# SenseBox-Eye_v1_4.net
KiCad netlist of a schematic drawn in EAGLE
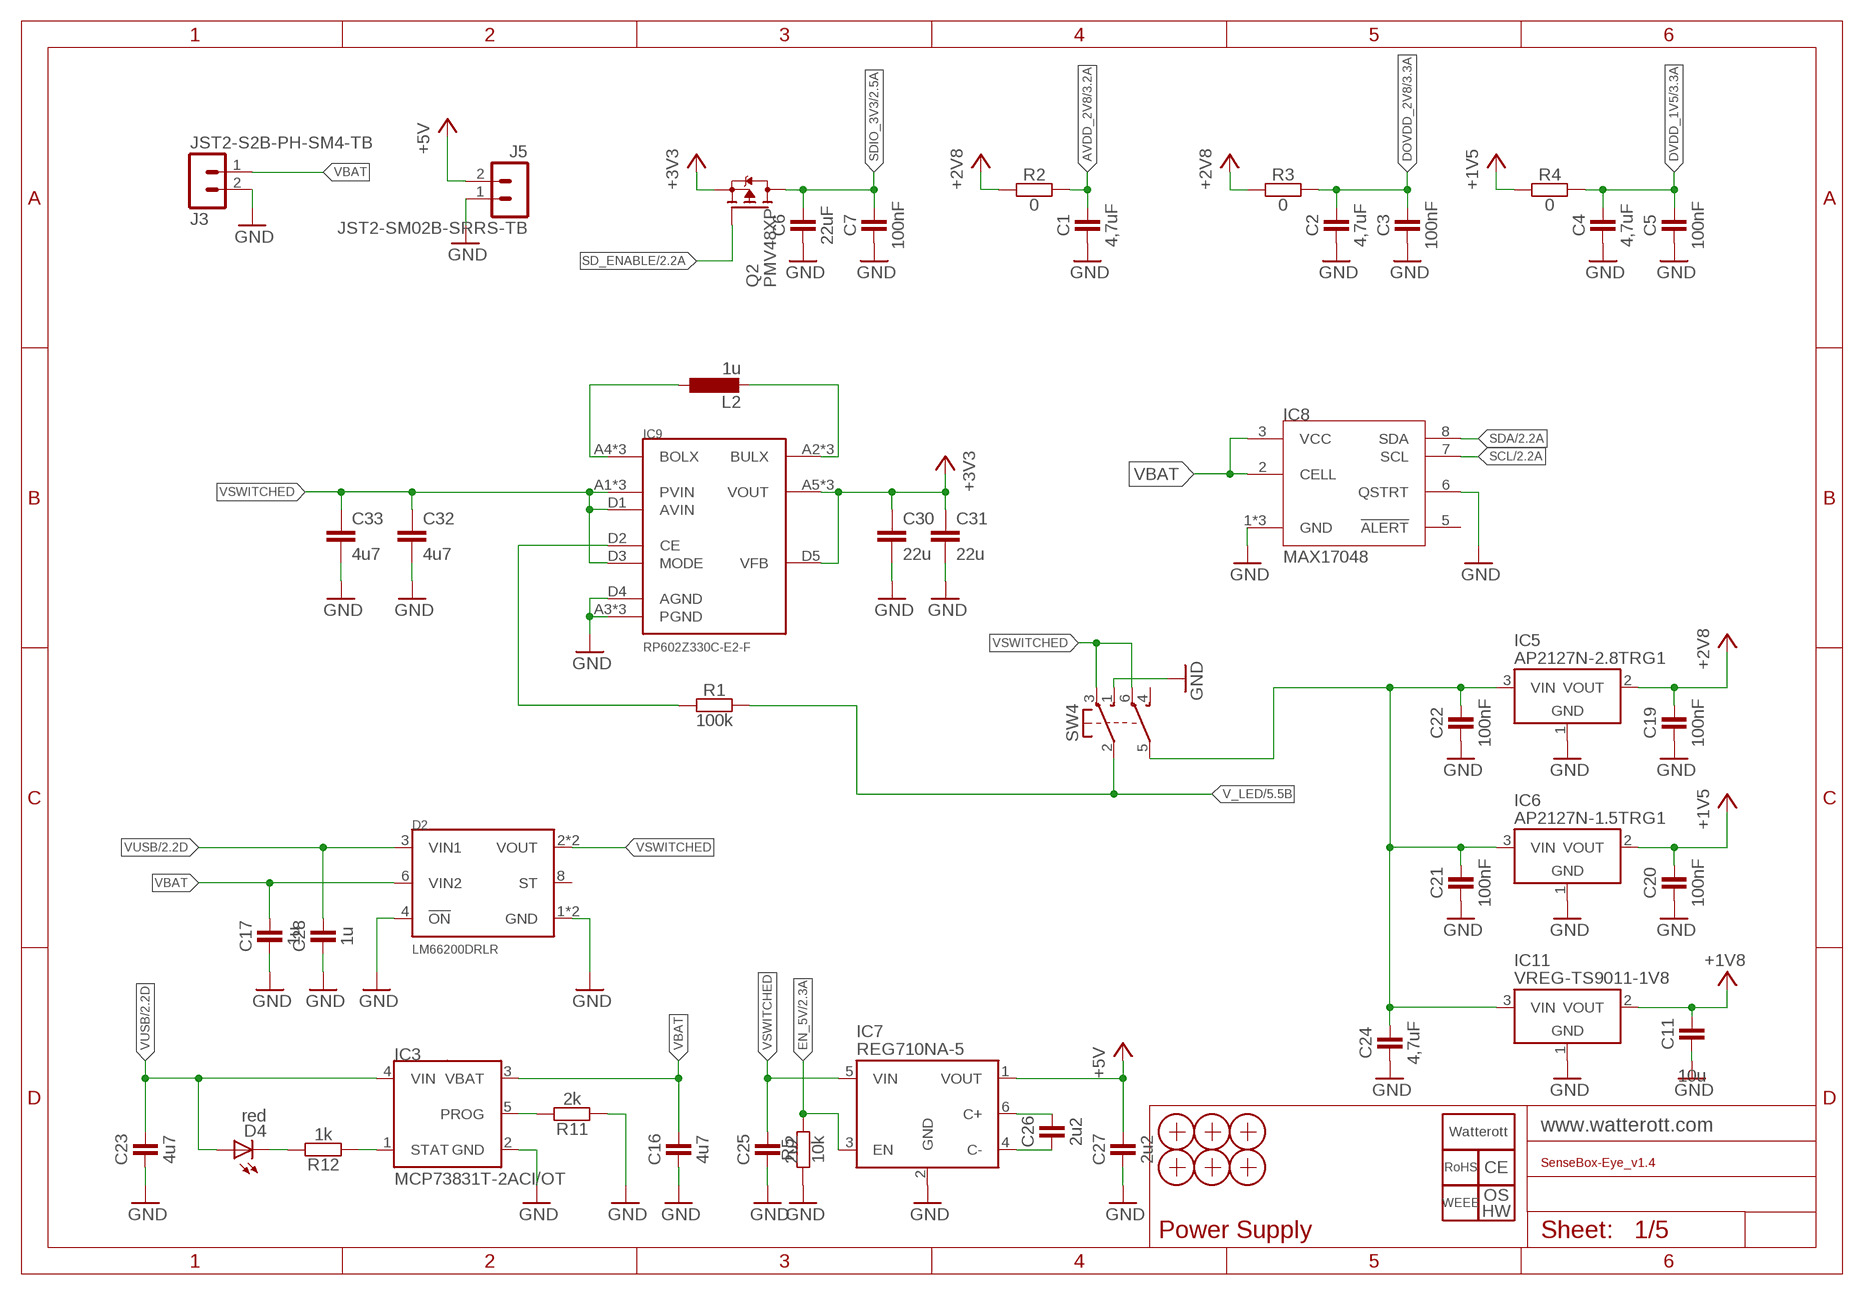
[diagram p0: schematic, sheet 1]
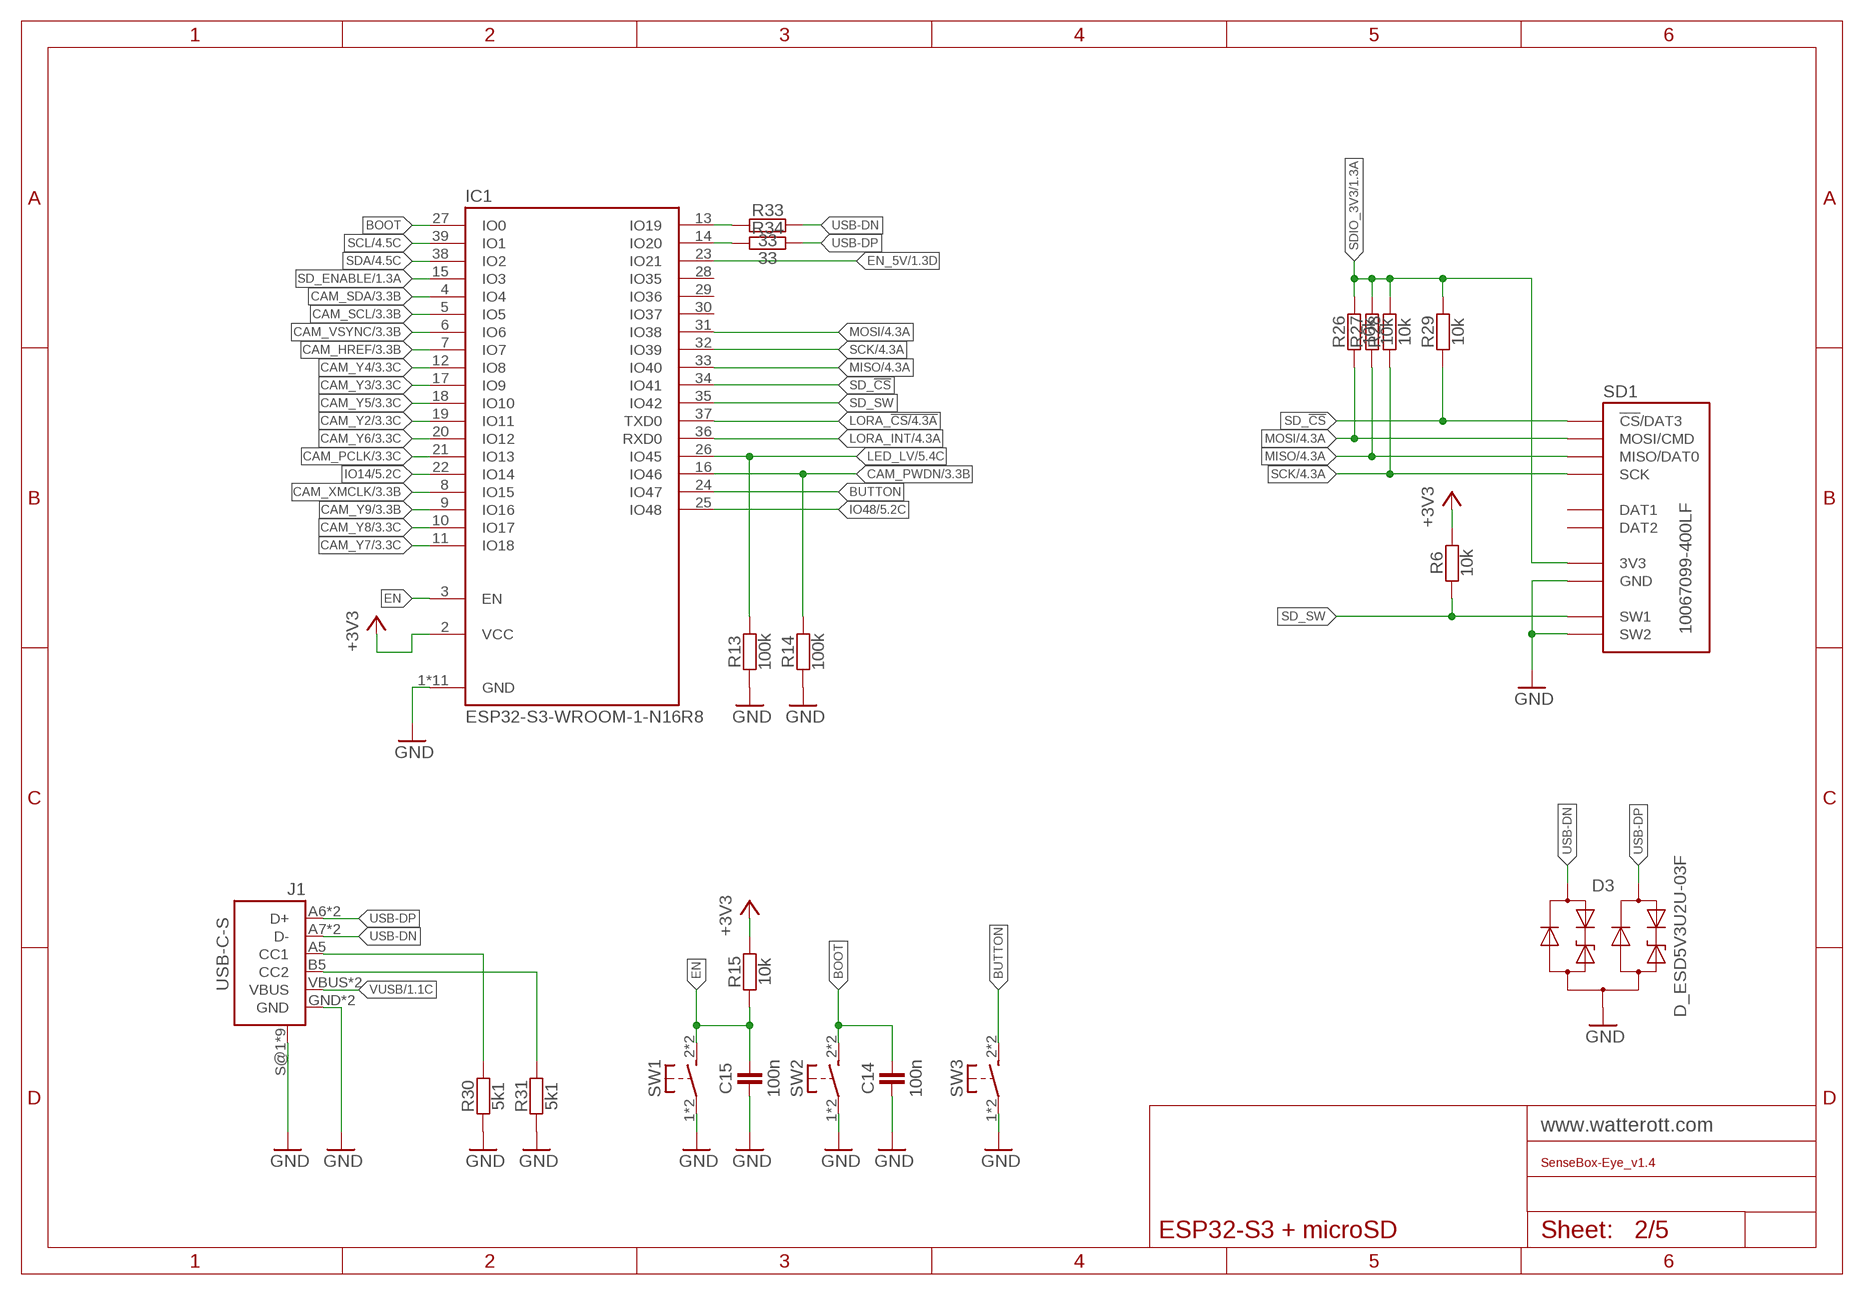
[diagram p1: schematic, sheet 2]
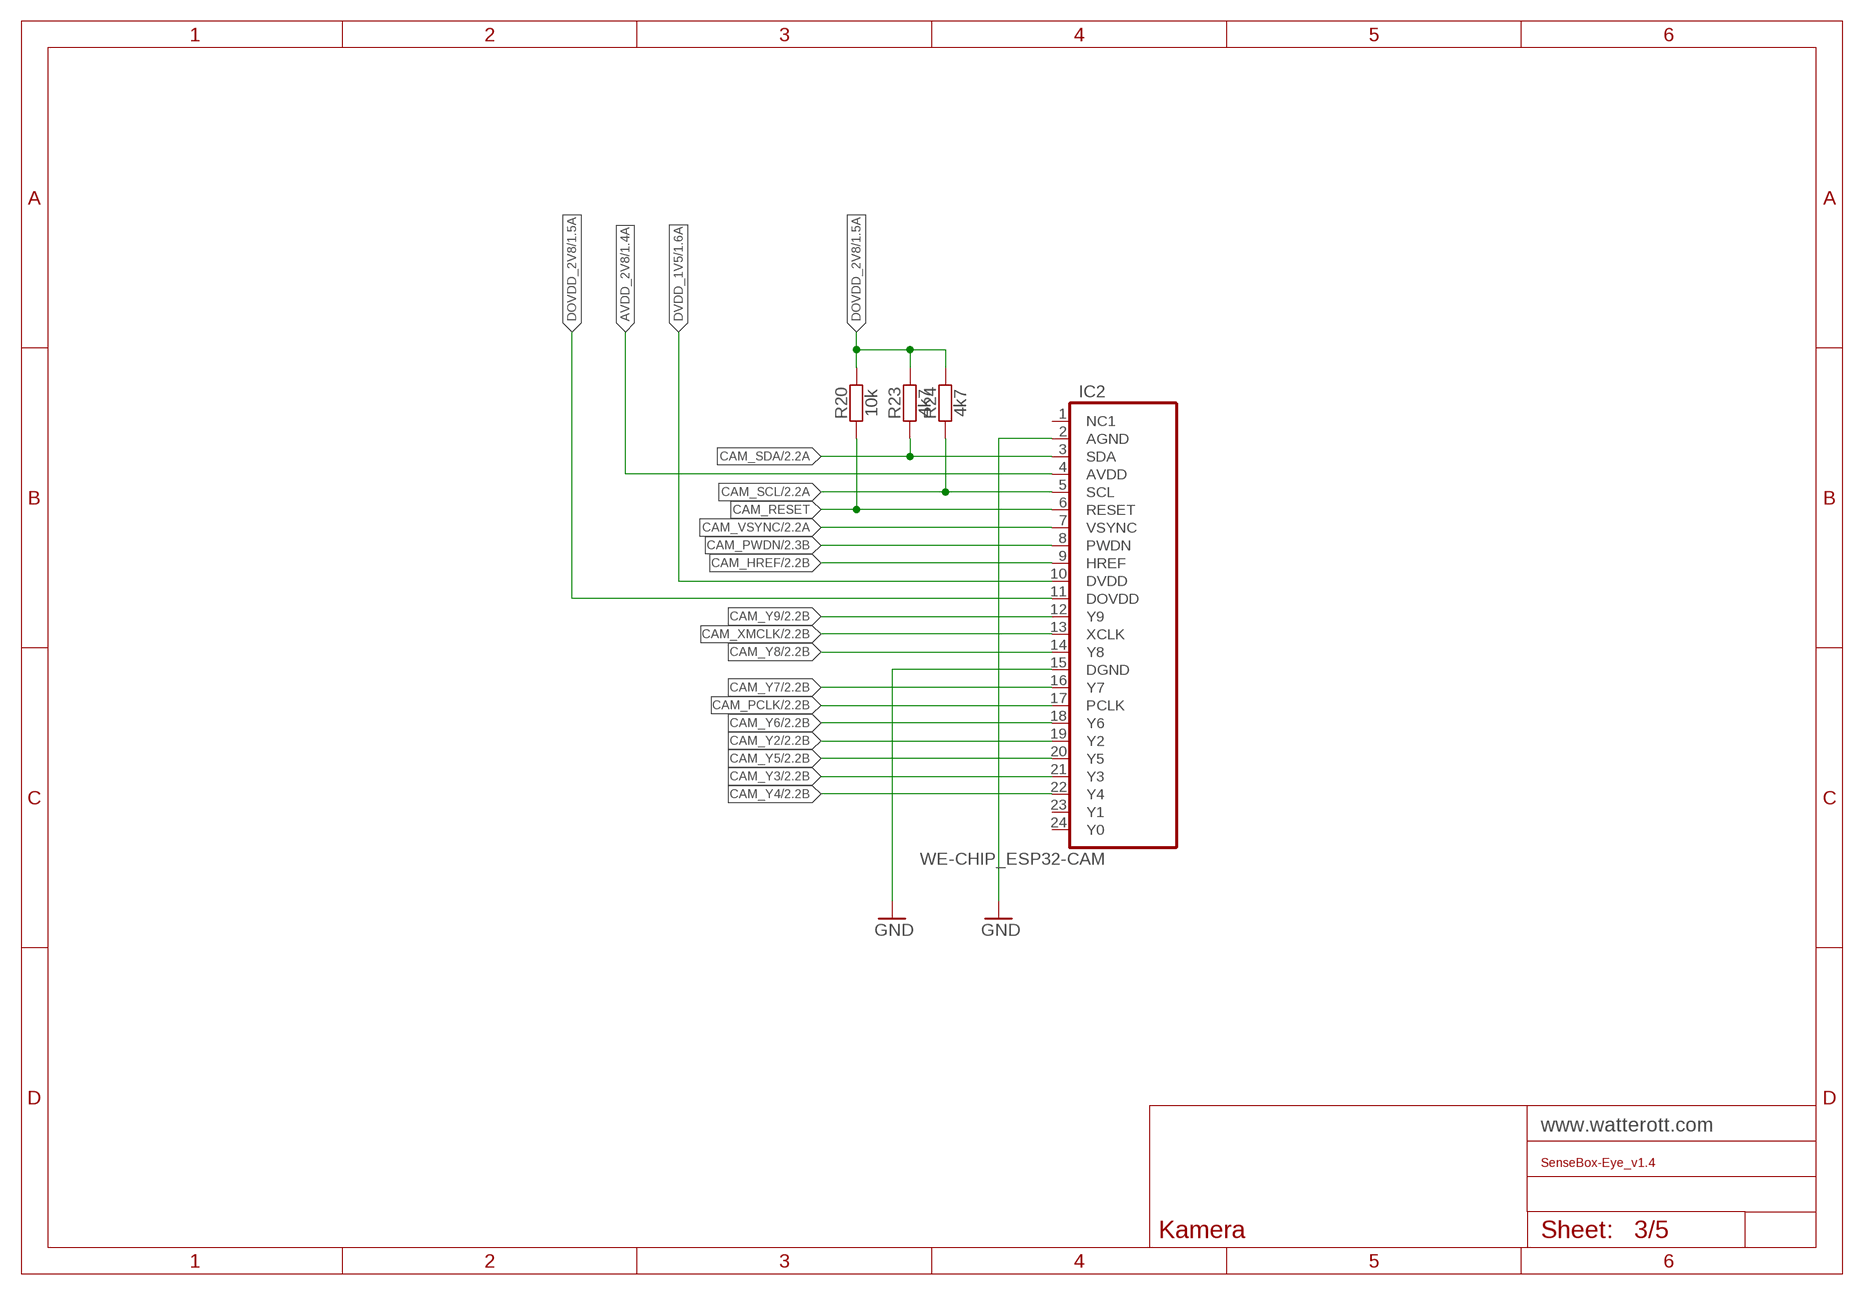
[diagram p2: schematic, sheet 3]
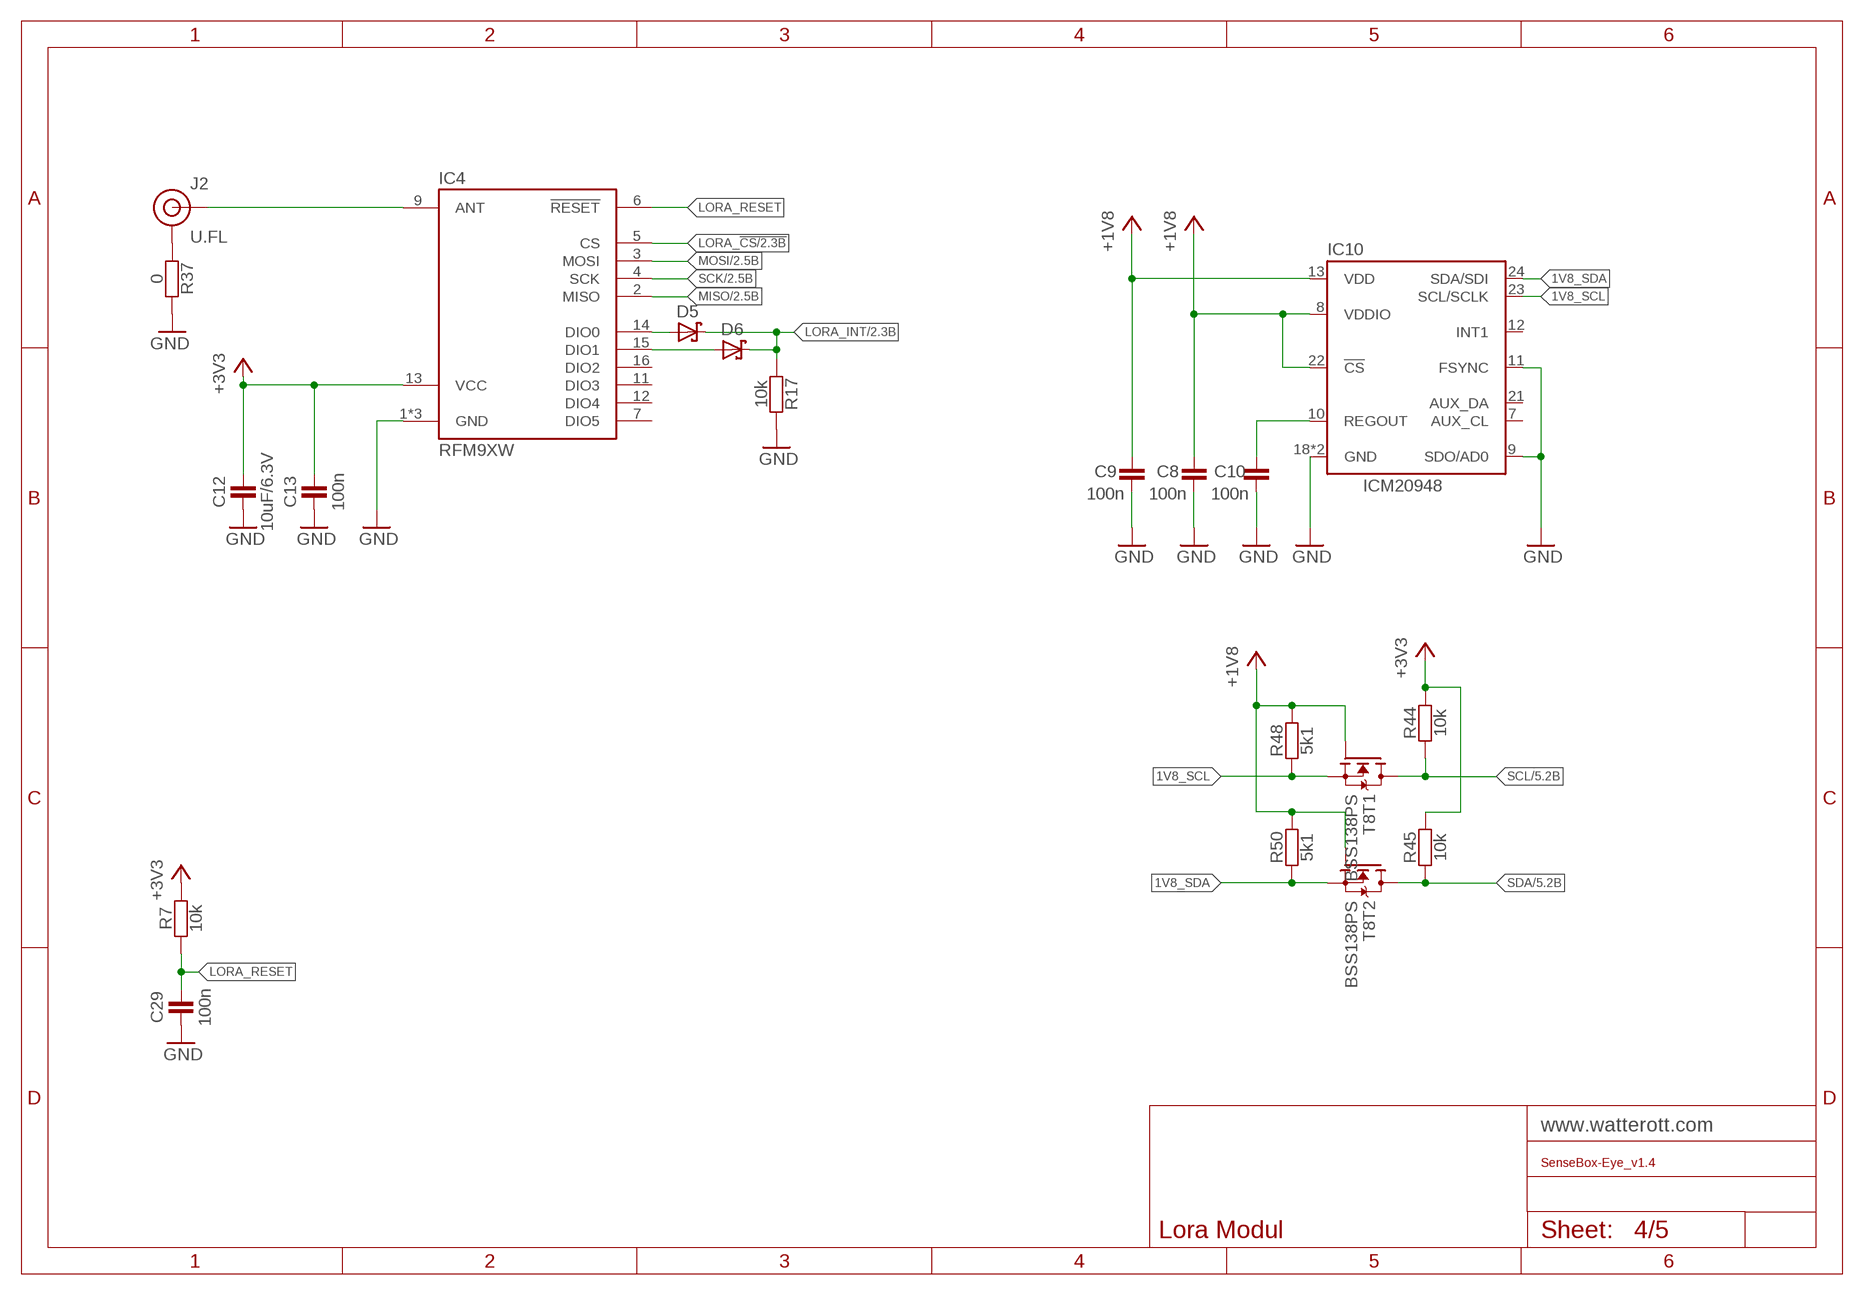
[diagram p3: schematic, sheet 4]
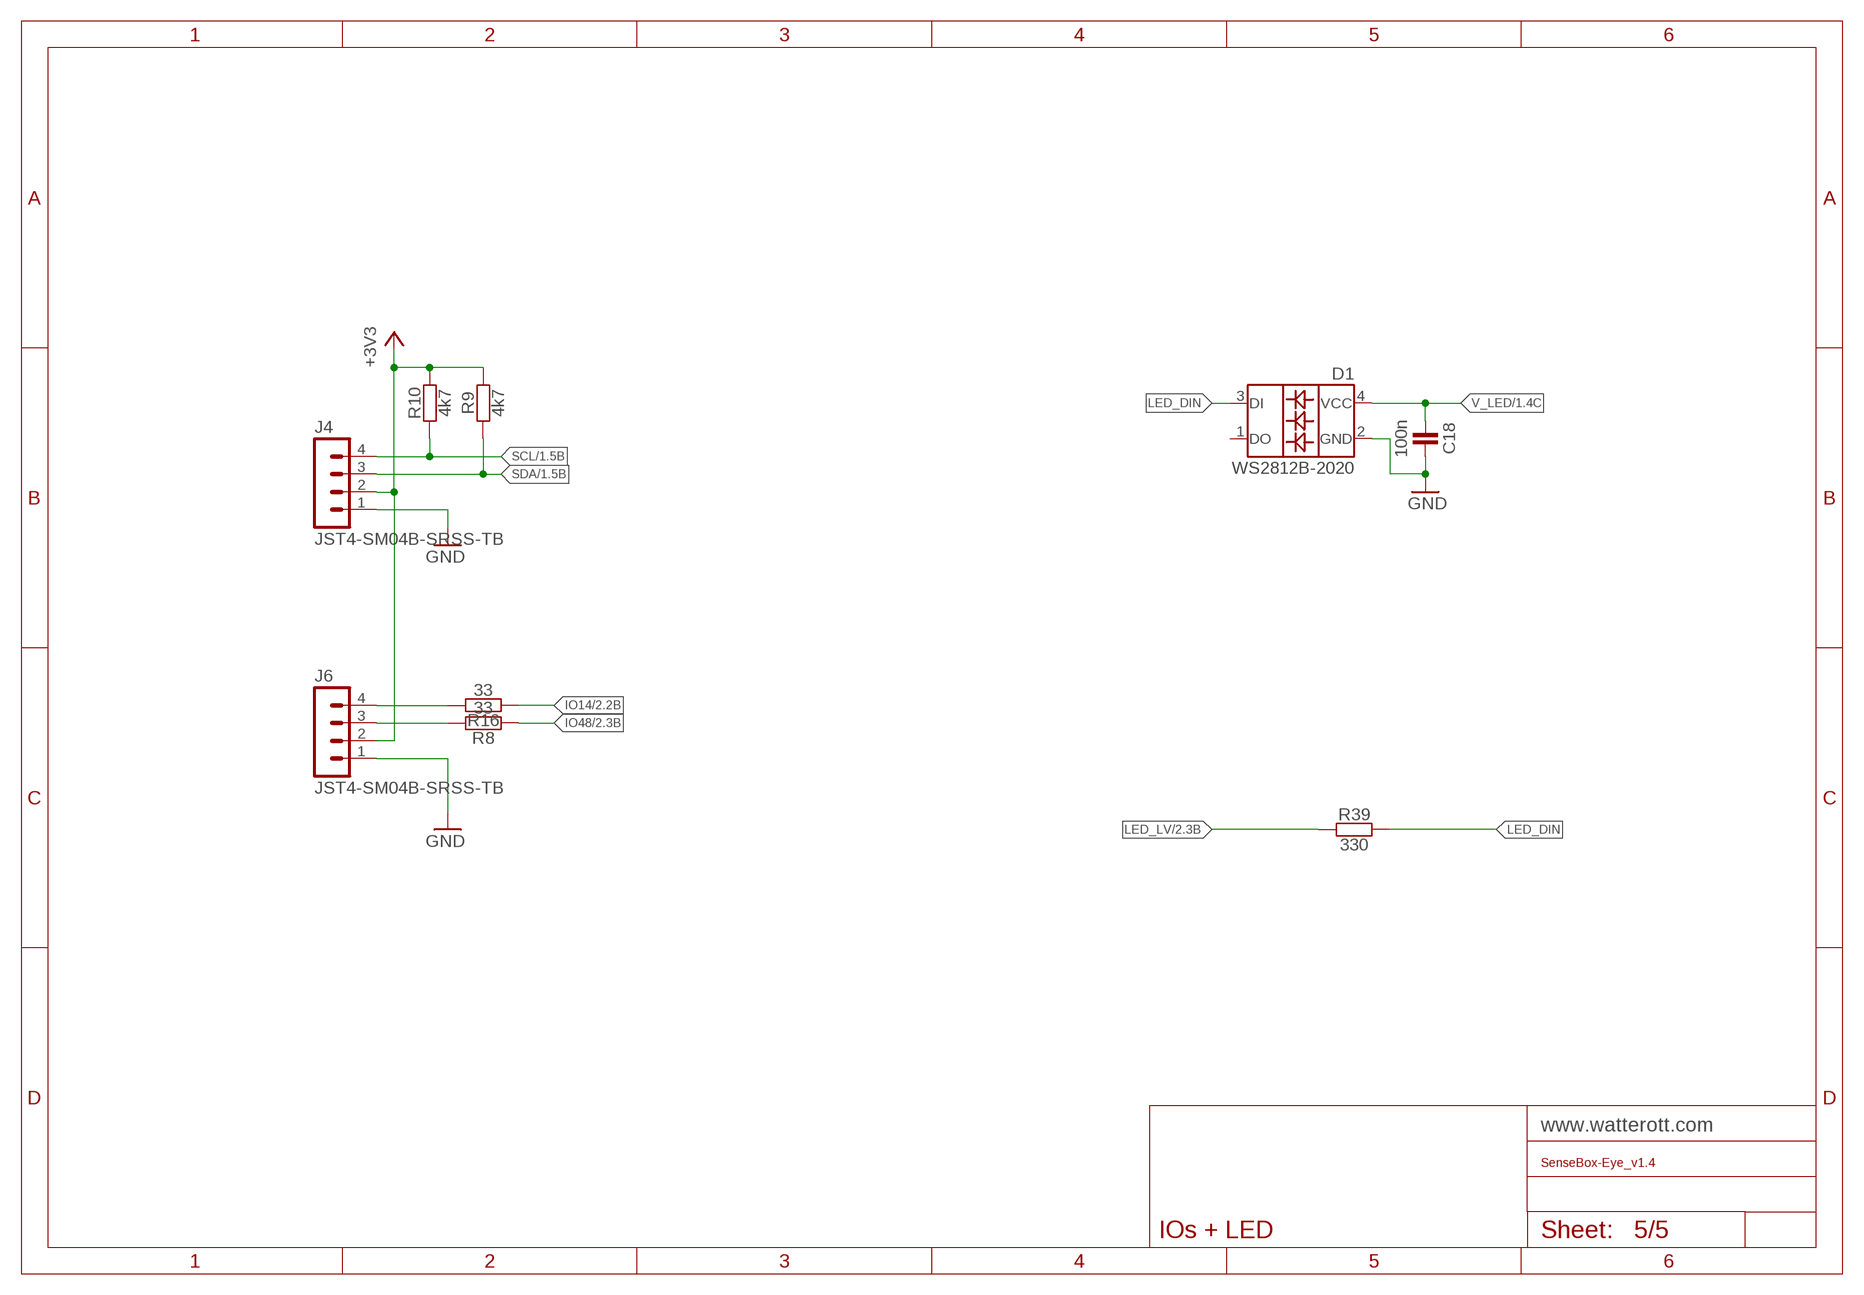
[diagram p4: schematic, sheet 5]

(export (version "E")
  (design (tool "Eeschema 10.0.6"))
  (components
    (comp (ref "IC2")
      (value "WE-CHIP_ESP32-CAM")
      (footprint "eagle-import:WE-CHIP_FPC24-0.5-CAM")
      (libsource (lib "eagle-import") (part "WE-CHIP_ESP32-CAM"))
    )
    (comp (ref "R20")
      (value "10k")
      (footprint "eagle-import:C0402")
      (libsource (lib "eagle-import") (part "RESISTOR-0402"))
    )
    (comp (ref "R23")
      (value "4k7")
      (footprint "eagle-import:C0402")
      (libsource (lib "eagle-import") (part "RESISTOR-0402"))
    )
    (comp (ref "R24")
      (value "4k7")
      (footprint "eagle-import:C0402")
      (libsource (lib "eagle-import") (part "RESISTOR-0402"))
    )
    (comp (ref "C14")
      (value "100n")
      (footprint "eagle-import:C0402")
      (libsource (lib "eagle-import") (part "CAPACITOR-0402"))
    )
    (comp (ref "C15")
      (value "100n")
      (footprint "eagle-import:C0402")
      (libsource (lib "eagle-import") (part "CAPACITOR-0402"))
    )
    (comp (ref "D3")
      (value "D_ESD5V3U2U-03F")
      (footprint "eagle-import:SOT723")
      (libsource (lib "eagle-import") (part "D_ESD5V3U2U-03F"))
    )
    (comp (ref "IC1")
      (value "ESP32-S3-WROOM-1-N16R8")
      (footprint "eagle-import:ESP32-S3-WROOM-1")
      (libsource (lib "eagle-import") (part "ESP32_S3-WROOM-1"))
    )
    (comp (ref "J1")
      (value "USB-C-S")
      (footprint "eagle-import:USB-C-S")
      (libsource (lib "eagle-import") (part "USB-C-S"))
    )
    (comp (ref "R6")
      (value "10k")
      (footprint "eagle-import:C0402")
      (libsource (lib "eagle-import") (part "RESISTOR-0402"))
    )
    (comp (ref "R13")
      (value "100k")
      (footprint "eagle-import:C0402")
      (libsource (lib "eagle-import") (part "RESISTOR-0402"))
    )
    (comp (ref "R14")
      (value "100k")
      (footprint "eagle-import:C0402")
      (libsource (lib "eagle-import") (part "RESISTOR-0402"))
    )
    (comp (ref "R15")
      (value "10k")
      (footprint "eagle-import:C0402")
      (libsource (lib "eagle-import") (part "RESISTOR-0402"))
    )
    (comp (ref "R26")
      (value "10k")
      (footprint "eagle-import:C0402")
      (libsource (lib "eagle-import") (part "RESISTOR-0402"))
    )
    (comp (ref "R27")
      (value "10k")
      (footprint "eagle-import:C0402")
      (libsource (lib "eagle-import") (part "RESISTOR-0402"))
    )
    (comp (ref "R28")
      (value "10k")
      (footprint "eagle-import:C0402")
      (libsource (lib "eagle-import") (part "RESISTOR-0402"))
    )
    (comp (ref "R29")
      (value "10k")
      (footprint "eagle-import:C0402")
      (libsource (lib "eagle-import") (part "RESISTOR-0402"))
    )
    (comp (ref "R30")
      (value "5k1")
      (footprint "eagle-import:C0402")
      (libsource (lib "eagle-import") (part "RESISTOR-0402"))
    )
    (comp (ref "R31")
      (value "5k1")
      (footprint "eagle-import:C0402")
      (libsource (lib "eagle-import") (part "RESISTOR-0402"))
    )
    (comp (ref "R33")
      (value "33")
      (footprint "eagle-import:C0402")
      (libsource (lib "eagle-import") (part "RESISTOR-0402"))
    )
    (comp (ref "R34")
      (value "33")
      (footprint "eagle-import:C0402")
      (libsource (lib "eagle-import") (part "RESISTOR-0402"))
    )
    (comp (ref "SD1")
      (value "10067099-400LF")
      (footprint "eagle-import:SD_47309XXXX")
      (libsource (lib "eagle-import") (part "SD-CARD-MSD47"))
    )
    (comp (ref "SW1")
      (value "SW-TACTILE-TL3305")
      (footprint "eagle-import:TL3305")
      (libsource (lib "eagle-import") (part "SW-TACTILE-TL3305"))
    )
    (comp (ref "SW2")
      (value "SW-TACTILE-TL3305")
      (footprint "eagle-import:TL3305")
      (libsource (lib "eagle-import") (part "SW-TACTILE-TL3305"))
    )
    (comp (ref "SW3")
      (value "SW-TACTILE-TL3305")
      (footprint "eagle-import:TL3305")
      (libsource (lib "eagle-import") (part "SW-TACTILE-TL3305"))
    )
    (comp (ref "C18")
      (value "100n")
      (footprint "eagle-import:C0402")
      (libsource (lib "eagle-import") (part "CAPACITOR-0402"))
    )
    (comp (ref "D1")
      (value "WS2812B-2020")
      (footprint "eagle-import:WS2812_2020")
      (libsource (lib "eagle-import") (part "WS2812B-2020"))
    )
    (comp (ref "J4")
      (value "JST4-SM04B-SRSS-TB")
      (footprint "eagle-import:JST_SM04B-SRSS-TB")
      (libsource (lib "eagle-import") (part "JST4-SM04B-SRSS-TB"))
    )
    (comp (ref "J6")
      (value "JST4-SM04B-SRSS-TB")
      (footprint "eagle-import:JST_SM04B-SRSS-TB")
      (libsource (lib "eagle-import") (part "JST4-SM04B-SRSS-TB"))
    )
    (comp (ref "R8")
      (value "33")
      (footprint "eagle-import:C0402")
      (libsource (lib "eagle-import") (part "RESISTOR-0402"))
    )
    (comp (ref "R9")
      (value "4k7")
      (footprint "eagle-import:C0402")
      (libsource (lib "eagle-import") (part "RESISTOR-0402"))
    )
    (comp (ref "R10")
      (value "4k7")
      (footprint "eagle-import:C0402")
      (libsource (lib "eagle-import") (part "RESISTOR-0402"))
    )
    (comp (ref "R16")
      (value "33")
      (footprint "eagle-import:C0402")
      (libsource (lib "eagle-import") (part "RESISTOR-0402"))
    )
    (comp (ref "R39")
      (value "330")
      (footprint "eagle-import:C0402")
      (libsource (lib "eagle-import") (part "RESISTOR-0402"))
    )
    (comp (ref "C1")
      (value "4,7uF")
      (footprint "eagle-import:C0402")
      (libsource (lib "eagle-import") (part "CAPACITOR-0402"))
    )
    (comp (ref "C2")
      (value "4,7uF")
      (footprint "eagle-import:C0402")
      (libsource (lib "eagle-import") (part "CAPACITOR-0402"))
    )
    (comp (ref "C3")
      (value "100nF")
      (footprint "eagle-import:C0402")
      (libsource (lib "eagle-import") (part "CAPACITOR-0402"))
    )
    (comp (ref "C4")
      (value "4,7uF")
      (footprint "eagle-import:C0402")
      (libsource (lib "eagle-import") (part "CAPACITOR-0402"))
    )
    (comp (ref "C5")
      (value "100nF")
      (footprint "eagle-import:C0402")
      (libsource (lib "eagle-import") (part "CAPACITOR-0402"))
    )
    (comp (ref "C6")
      (value "22uF")
      (footprint "eagle-import:C0402")
      (libsource (lib "eagle-import") (part "CAPACITOR-0402"))
    )
    (comp (ref "C7")
      (value "100nF")
      (footprint "eagle-import:C0402")
      (libsource (lib "eagle-import") (part "CAPACITOR-0402"))
    )
    (comp (ref "C11")
      (value "10u")
      (footprint "eagle-import:C0402")
      (libsource (lib "eagle-import") (part "CAPACITOR-0402"))
    )
    (comp (ref "C16")
      (value "4u7")
      (footprint "eagle-import:C0402")
      (libsource (lib "eagle-import") (part "CAPACITOR-0402"))
    )
    (comp (ref "C17")
      (value "1u")
      (footprint "eagle-import:C0402")
      (libsource (lib "eagle-import") (part "CAPACITOR-0402"))
    )
    (comp (ref "C19")
      (value "100nF")
      (footprint "eagle-import:C0402")
      (libsource (lib "eagle-import") (part "CAPACITOR-0402"))
    )
    (comp (ref "C20")
      (value "100nF")
      (footprint "eagle-import:C0402")
      (libsource (lib "eagle-import") (part "CAPACITOR-0402"))
    )
    (comp (ref "C21")
      (value "100nF")
      (footprint "eagle-import:C0402")
      (libsource (lib "eagle-import") (part "CAPACITOR-0402"))
    )
    (comp (ref "C22")
      (value "100nF")
      (footprint "eagle-import:C0402")
      (libsource (lib "eagle-import") (part "CAPACITOR-0402"))
    )
    (comp (ref "C23")
      (value "4u7")
      (footprint "eagle-import:C0402")
      (libsource (lib "eagle-import") (part "CAPACITOR-0402"))
    )
    (comp (ref "C24")
      (value "4,7uF")
      (footprint "eagle-import:C0402")
      (libsource (lib "eagle-import") (part "CAPACITOR-0402"))
    )
    (comp (ref "C25")
      (value "2u2")
      (footprint "eagle-import:C0402")
      (libsource (lib "eagle-import") (part "CAPACITOR-0402"))
    )
    (comp (ref "C26")
      (value "2u2")
      (footprint "eagle-import:C0402")
      (libsource (lib "eagle-import") (part "CAPACITOR-0402"))
    )
    (comp (ref "C27")
      (value "2u2")
      (footprint "eagle-import:C0402")
      (libsource (lib "eagle-import") (part "CAPACITOR-0402"))
    )
    (comp (ref "C28")
      (value "1u")
      (footprint "eagle-import:C0402")
      (libsource (lib "eagle-import") (part "CAPACITOR-0402"))
    )
    (comp (ref "C30")
      (value "22u")
      (footprint "eagle-import:0805N")
      (fields (field (name "VOLTAGE") "6V3"))
      (libsource (lib "eagle-import") (part "C_0805N_22U"))
    )
    (comp (ref "C31")
      (value "22u")
      (footprint "eagle-import:0805N")
      (fields (field (name "VOLTAGE") "6V3"))
      (libsource (lib "eagle-import") (part "C_0805N_22U"))
    )
    (comp (ref "C32")
      (value "4u7")
      (footprint "eagle-import:0603N")
      (fields (field (name "VOLTAGE") "6V3"))
      (libsource (lib "eagle-import") (part "C_0603N_4U7"))
    )
    (comp (ref "C33")
      (value "4u7")
      (footprint "eagle-import:0603N")
      (fields (field (name "VOLTAGE") "6V3"))
      (libsource (lib "eagle-import") (part "C_0603N_4U7"))
    )
    (comp (ref "D2")
      (value "LM66200DRLR")
      (footprint "eagle-import:SOT-5X3")
      (libsource (lib "eagle-import") (part "LM66200"))
    )
    (comp (ref "D4")
      (value "red")
      (footprint "eagle-import:0603N")
      (libsource (lib "eagle-import") (part "LED_0603N_RED"))
    )
    (comp (ref "IC3")
      (value "MCP73831T-2ACI/OT")
      (footprint "eagle-import:SOT23-5")
      (libsource (lib "eagle-import") (part "MCP73831_SOT23-5_MCP73831T-2ACI/OT"))
    )
    (comp (ref "IC5")
      (value "AP2127N-2.8TRG1")
      (footprint "eagle-import:SOT23")
      (libsource (lib "eagle-import") (part "VREG-TS9011-3V3"))
    )
    (comp (ref "IC6")
      (value "AP2127N-1.5TRG1")
      (footprint "eagle-import:SOT23")
      (libsource (lib "eagle-import") (part "VREG-TS9011-3V3"))
    )
    (comp (ref "IC7")
      (value "REG710NA-5")
      (footprint "eagle-import:SOT23-6")
      (libsource (lib "eagle-import") (part "REG710NA-5"))
    )
    (comp (ref "IC8")
      (value "MAX17048")
      (footprint "eagle-import:UDFN8_2020")
      (libsource (lib "eagle-import") (part "MAX1704X"))
    )
    (comp (ref "IC9")
      (value "RP602Z330C-E2-F")
      (footprint "eagle-import:WLCSP-20-P1")
      (libsource (lib "eagle-import") (part "RP602_WLCSP-20-P1_RP602Z330C-E2-F"))
    )
    (comp (ref "IC11")
      (value "VREG-TS9011-1V8")
      (footprint "eagle-import:SOT23")
      (libsource (lib "eagle-import") (part "VREG-TS9011-1V8"))
    )
    (comp (ref "J3")
      (value "JST2-S2B-PH-SM4-TB")
      (footprint "eagle-import:JST_S2B-PH-SM4-TB")
      (libsource (lib "eagle-import") (part "JST2-S2B-PH-SM4-TB"))
    )
    (comp (ref "J5")
      (value "JST2-SM02B-SRRS-TB")
      (footprint "eagle-import:JST_SM02B-SRSS-TB")
      (libsource (lib "eagle-import") (part "JST2-SM02B-SRRS-TB"))
    )
    (comp (ref "L2")
      (value "1u")
      (footprint "eagle-import:5040")
      (libsource (lib "eagle-import") (part "L_5040_WE-LQS-1U"))
    )
    (comp (ref "LOGO2")
      (value "LOGO_CE-5")
      (footprint "eagle-import:CE_5MM")
      (libsource (lib "eagle-import") (part "LOGO_CE-5"))
    )
    (comp (ref "LOGO3")
      (value "LOGO_OSHW-2")
      (footprint "eagle-import:OSHW_2MM")
      (libsource (lib "eagle-import") (part "LOGO_OSHW-2"))
    )
    (comp (ref "LOGO4")
      (value "LOGO_ROHS-2")
      (footprint "eagle-import:ROHS_2MM")
      (libsource (lib "eagle-import") (part "LOGO_ROHS-2"))
    )
    (comp (ref "LOGO5")
      (value "LOGO_WEEE-4")
      (footprint "eagle-import:WEEE_4MM")
      (libsource (lib "eagle-import") (part "LOGO_WEEE-4"))
    )
    (comp (ref "LOGO6")
      (value "LOGO_SPARK-2")
      (footprint "eagle-import:SPARK_2MM")
      (libsource (lib "eagle-import") (part "LOGO_SPARK-2"))
    )
    (comp (ref "Q2")
      (value "PMV48XP")
      (footprint "eagle-import:SOT23")
      (fields (field (name "VOLTAGE") "20"))
      (libsource (lib "eagle-import") (part "MOSFET-P_SOT23'_PMV48XP"))
    )
    (comp (ref "R1")
      (value "100k")
      (footprint "eagle-import:C0402")
      (libsource (lib "eagle-import") (part "RESISTOR-0402"))
    )
    (comp (ref "R2")
      (value "0")
      (footprint "eagle-import:C0402")
      (libsource (lib "eagle-import") (part "RESISTOR-0402"))
    )
    (comp (ref "R3")
      (value "0")
      (footprint "eagle-import:C0402")
      (libsource (lib "eagle-import") (part "RESISTOR-0402"))
    )
    (comp (ref "R4")
      (value "0")
      (footprint "eagle-import:C0402")
      (libsource (lib "eagle-import") (part "RESISTOR-0402"))
    )
    (comp (ref "R5")
      (value "10k")
      (footprint "eagle-import:C0402")
      (libsource (lib "eagle-import") (part "RESISTOR-0402"))
    )
    (comp (ref "R11")
      (value "2k")
      (footprint "eagle-import:C0402")
      (libsource (lib "eagle-import") (part "RESISTOR-0402"))
    )
    (comp (ref "R12")
      (value "1k")
      (footprint "eagle-import:C0402")
      (libsource (lib "eagle-import") (part "RESISTOR-0402"))
    )
    (comp (ref "SW4")
      (value "SW-2UM-CUS22B")
      (footprint "eagle-import:CUS22B")
      (libsource (lib "eagle-import") (part "SW-2UM-CUS22B"))
    )
    (comp (ref "X1")
      (value "PASSER-04")
      (footprint "eagle-import:PASSER_04MM")
      (libsource (lib "eagle-import") (part "PASSER-04"))
    )
    (comp (ref "X2")
      (value "PASSER-04")
      (footprint "eagle-import:PASSER_04MM")
      (libsource (lib "eagle-import") (part "PASSER-04"))
    )
    (comp (ref "X3")
      (value "PASSER-04")
      (footprint "eagle-import:PASSER_04MM")
      (libsource (lib "eagle-import") (part "PASSER-04"))
    )
    (comp (ref "X4")
      (value "PASSER-04")
      (footprint "eagle-import:PASSER_04MM")
      (libsource (lib "eagle-import") (part "PASSER-04"))
    )
    (comp (ref "X5")
      (value "PASSER-04")
      (footprint "eagle-import:PASSER_04MM")
      (libsource (lib "eagle-import") (part "PASSER-04"))
    )
    (comp (ref "X6")
      (value "PASSER-04")
      (footprint "eagle-import:PASSER_04MM")
      (libsource (lib "eagle-import") (part "PASSER-04"))
    )
    (comp (ref "C8")
      (value "100n")
      (footprint "eagle-import:C0402")
      (libsource (lib "eagle-import") (part "CAPACITOR-0402"))
    )
    (comp (ref "C9")
      (value "100n")
      (footprint "eagle-import:C0402")
      (libsource (lib "eagle-import") (part "CAPACITOR-0402"))
    )
    (comp (ref "C10")
      (value "100n")
      (footprint "eagle-import:C0402")
      (libsource (lib "eagle-import") (part "CAPACITOR-0402"))
    )
    (comp (ref "C12")
      (value "10uF/6.3V")
      (footprint "eagle-import:C0402")
      (libsource (lib "eagle-import") (part "CAPACITOR-0402"))
    )
    (comp (ref "C13")
      (value "100n")
      (footprint "eagle-import:C0402")
      (libsource (lib "eagle-import") (part "CAPACITOR-0402"))
    )
    (comp (ref "C29")
      (value "100n")
      (footprint "eagle-import:C0402")
      (libsource (lib "eagle-import") (part "CAPACITOR-0402"))
    )
    (comp (ref "D5")
      (value "D_SCHOTTKY-SOD523")
      (footprint "eagle-import:SOD523")
      (libsource (lib "eagle-import") (part "D_SCHOTTKY-SOD523"))
    )
    (comp (ref "D6")
      (value "D_SCHOTTKY-SOD523")
      (footprint "eagle-import:SOD523")
      (libsource (lib "eagle-import") (part "D_SCHOTTKY-SOD523"))
    )
    (comp (ref "IC4")
      (value "RFM9XW")
      (footprint "eagle-import:RFM9X")
      (libsource (lib "eagle-import") (part "RFM9XW"))
    )
    (comp (ref "IC10")
      (value "ICM20948")
      (footprint "eagle-import:QFN24-3X3")
      (libsource (lib "eagle-import") (part "ICM20948"))
    )
    (comp (ref "J2")
      (value "U.FL")
      (footprint "eagle-import:U.FL")
      (libsource (lib "eagle-import") (part "U.FL"))
    )
    (comp (ref "R7")
      (value "10k")
      (footprint "eagle-import:C0402")
      (libsource (lib "eagle-import") (part "RESISTOR-0402"))
    )
    (comp (ref "R17")
      (value "10k")
      (footprint "eagle-import:C0402")
      (libsource (lib "eagle-import") (part "RESISTOR-0402"))
    )
    (comp (ref "R37")
      (value "0")
      (footprint "eagle-import:C0402")
      (libsource (lib "eagle-import") (part "RESISTOR-0402"))
    )
    (comp (ref "R44")
      (value "10k")
      (footprint "eagle-import:C0402")
      (libsource (lib "eagle-import") (part "RESISTOR-0402"))
    )
    (comp (ref "R45")
      (value "10k")
      (footprint "eagle-import:C0402")
      (libsource (lib "eagle-import") (part "RESISTOR-0402"))
    )
    (comp (ref "R48")
      (value "5k1")
      (footprint "eagle-import:C0402")
      (libsource (lib "eagle-import") (part "RESISTOR-0402"))
    )
    (comp (ref "R50")
      (value "5k1")
      (footprint "eagle-import:C0402")
      (libsource (lib "eagle-import") (part "RESISTOR-0402"))
    )
    (comp (ref "T8")
      (value "BSS138PS")
      (footprint "eagle-import:SOT363")
      (libsource (lib "eagle-import") (part "BSS138PS"))
    )
  )
  (nets
    (net (code "1") (name "+1V5") (class "Default")
      (node (ref "C20") (pin "2") (pinfunction "2_2") (pintype "passive"))
      (node (ref "IC6") (pin "2") (pinfunction "VOUT_2") (pintype "power_in"))
      (node (ref "R4") (pin "1") (pinfunction "1_1") (pintype "passive"))
    )
    (net (code "2") (name "+1V8") (class "Default")
      (node (ref "C11") (pin "2") (pinfunction "2_2") (pintype "passive"))
      (node (ref "C8") (pin "2") (pinfunction "2_2") (pintype "passive"))
      (node (ref "C9") (pin "2") (pinfunction "2_2") (pintype "passive"))
      (node (ref "IC10") (pin "13") (pinfunction "VDD_13") (pintype "power_in"))
      (node (ref "IC10") (pin "22") (pinfunction "~{CS}_22") (pintype "bidirectional"))
      (node (ref "IC10") (pin "8") (pinfunction "VDDIO_8") (pintype "power_in"))
      (node (ref "IC11") (pin "2") (pinfunction "VOUT_2") (pintype "power_in"))
      (node (ref "R48") (pin "2") (pinfunction "2_2") (pintype "passive"))
      (node (ref "R50") (pin "2") (pinfunction "2_2") (pintype "passive"))
      (node (ref "T8") (pin "2") (pinfunction "G_2") (pintype "passive"))
      (node (ref "T8") (pin "5") (pinfunction "G_5") (pintype "passive"))
    )
    (net (code "3") (name "+2V8") (class "Default")
      (node (ref "C19") (pin "2") (pinfunction "2_2") (pintype "passive"))
      (node (ref "IC5") (pin "2") (pinfunction "VOUT_2") (pintype "power_in"))
      (node (ref "R2") (pin "1") (pinfunction "1_1") (pintype "passive"))
      (node (ref "R3") (pin "1") (pinfunction "1_1") (pintype "passive"))
    )
    (net (code "4") (name "+3V3") (class "Default")
      (node (ref "C12") (pin "2") (pinfunction "2_2") (pintype "passive"))
      (node (ref "C13") (pin "2") (pinfunction "2_2") (pintype "passive"))
      (node (ref "C30") (pin "1") (pinfunction "1_1") (pintype "passive"))
      (node (ref "C31") (pin "1") (pinfunction "1_1") (pintype "passive"))
      (node (ref "IC1") (pin "2") (pinfunction "VCC_2") (pintype "power_in"))
      (node (ref "IC4") (pin "13") (pinfunction "VCC_13") (pintype "power_in"))
      (node (ref "IC9") (pin "A5") (pinfunction "VOUT_A5") (pintype "power_in"))
      (node (ref "IC9") (pin "B5") (pinfunction "VOUT_B5") (pintype "power_in"))
      (node (ref "IC9") (pin "C5") (pinfunction "VOUT_C5") (pintype "power_in"))
      (node (ref "IC9") (pin "D5") (pinfunction "VFB_D5") (pintype "input"))
      (node (ref "J4") (pin "2") (pinfunction "2_2") (pintype "passive"))
      (node (ref "J6") (pin "2") (pinfunction "2_2") (pintype "passive"))
      (node (ref "Q2") (pin "2") (pinfunction "S_2") (pintype "passive"))
      (node (ref "R10") (pin "1") (pinfunction "1_1") (pintype "passive"))
      (node (ref "R15") (pin "2") (pinfunction "2_2") (pintype "passive"))
      (node (ref "R44") (pin "2") (pinfunction "2_2") (pintype "passive"))
      (node (ref "R45") (pin "2") (pinfunction "2_2") (pintype "passive"))
      (node (ref "R6") (pin "2") (pinfunction "2_2") (pintype "passive"))
      (node (ref "R7") (pin "2") (pinfunction "2_2") (pintype "passive"))
      (node (ref "R9") (pin "1") (pinfunction "1_1") (pintype "passive"))
    )
    (net (code "5") (name "+5V") (class "Default")
      (node (ref "C27") (pin "2") (pinfunction "2_2") (pintype "passive"))
      (node (ref "IC7") (pin "1") (pinfunction "VOUT_1") (pintype "power_in"))
      (node (ref "J5") (pin "2") (pinfunction "2_2") (pintype "passive"))
    )
    (net (code "6") (name "1V8_SCL") (class "Default")
      (node (ref "IC10") (pin "23") (pinfunction "SCL/SCLK_23") (pintype "bidirectional"))
      (node (ref "R48") (pin "1") (pinfunction "1_1") (pintype "passive"))
      (node (ref "T8") (pin "1") (pinfunction "S_1") (pintype "passive"))
    )
    (net (code "7") (name "1V8_SDA") (class "Default")
      (node (ref "IC10") (pin "24") (pinfunction "SDA/SDI_24") (pintype "bidirectional"))
      (node (ref "R50") (pin "1") (pinfunction "1_1") (pintype "passive"))
      (node (ref "T8") (pin "4") (pinfunction "S_4") (pintype "passive"))
    )
    (net (code "8") (name "AVDD_2V8") (class "Default")
      (node (ref "C1") (pin "2") (pinfunction "2_2") (pintype "passive"))
      (node (ref "IC2") (pin "4") (pinfunction "AVDD_4") (pintype "bidirectional"))
      (node (ref "R2") (pin "2") (pinfunction "2_2") (pintype "passive"))
    )
    (net (code "9") (name "BOOT") (class "Default")
      (node (ref "C14") (pin "2") (pinfunction "2_2") (pintype "passive"))
      (node (ref "IC1") (pin "27") (pinfunction "IO0_27") (pintype "bidirectional"))
      (node (ref "SW2") (pin "2") (pinfunction "S1_2") (pintype "passive"))
      (node (ref "SW2") (pin "3") (pinfunction "S1_3") (pintype "passive"))
    )
    (net (code "10") (name "BUTTON") (class "Default")
      (node (ref "IC1") (pin "24") (pinfunction "IO47_24") (pintype "bidirectional"))
      (node (ref "SW3") (pin "2") (pinfunction "S1_2") (pintype "passive"))
      (node (ref "SW3") (pin "3") (pinfunction "S1_3") (pintype "passive"))
    )
    (net (code "11") (name "CAM_HREF") (class "Default")
      (node (ref "IC1") (pin "7") (pinfunction "IO7_7") (pintype "bidirectional"))
      (node (ref "IC2") (pin "9") (pinfunction "HREF_9") (pintype "bidirectional"))
    )
    (net (code "12") (name "CAM_PCLK") (class "Default")
      (node (ref "IC1") (pin "21") (pinfunction "IO13_21") (pintype "bidirectional"))
      (node (ref "IC2") (pin "17") (pinfunction "PCLK_17") (pintype "bidirectional"))
    )
    (net (code "13") (name "CAM_PWDN") (class "Default")
      (node (ref "IC1") (pin "16") (pinfunction "IO46_16") (pintype "bidirectional"))
      (node (ref "IC2") (pin "8") (pinfunction "PWDN_8") (pintype "bidirectional"))
      (node (ref "R14") (pin "2") (pinfunction "2_2") (pintype "passive"))
    )
    (net (code "14") (name "CAM_RESET") (class "Default")
      (node (ref "IC2") (pin "6") (pinfunction "RESET_6") (pintype "bidirectional"))
      (node (ref "R20") (pin "1") (pinfunction "1_1") (pintype "passive"))
    )
    (net (code "15") (name "CAM_SCL") (class "Default")
      (node (ref "IC1") (pin "5") (pinfunction "IO5_5") (pintype "bidirectional"))
      (node (ref "IC2") (pin "5") (pinfunction "SCL_5") (pintype "bidirectional"))
      (node (ref "R24") (pin "1") (pinfunction "1_1") (pintype "passive"))
    )
    (net (code "16") (name "CAM_SDA") (class "Default")
      (node (ref "IC1") (pin "4") (pinfunction "IO4_4") (pintype "bidirectional"))
      (node (ref "IC2") (pin "3") (pinfunction "SDA_3") (pintype "bidirectional"))
      (node (ref "R23") (pin "1") (pinfunction "1_1") (pintype "passive"))
    )
    (net (code "17") (name "CAM_VSYNC") (class "Default")
      (node (ref "IC1") (pin "6") (pinfunction "IO6_6") (pintype "bidirectional"))
      (node (ref "IC2") (pin "7") (pinfunction "VSYNC_7") (pintype "bidirectional"))
    )
    (net (code "18") (name "CAM_XMCLK") (class "Default")
      (node (ref "IC1") (pin "8") (pinfunction "IO15_8") (pintype "bidirectional"))
      (node (ref "IC2") (pin "13") (pinfunction "XCLK_13") (pintype "bidirectional"))
    )
    (net (code "19") (name "CAM_Y2") (class "Default")
      (node (ref "IC1") (pin "19") (pinfunction "IO11_19") (pintype "bidirectional"))
      (node (ref "IC2") (pin "19") (pinfunction "Y2_19") (pintype "bidirectional"))
    )
    (net (code "20") (name "CAM_Y3") (class "Default")
      (node (ref "IC1") (pin "17") (pinfunction "IO9_17") (pintype "bidirectional"))
      (node (ref "IC2") (pin "21") (pinfunction "Y3_21") (pintype "bidirectional"))
    )
    (net (code "21") (name "CAM_Y4") (class "Default")
      (node (ref "IC1") (pin "12") (pinfunction "IO8_12") (pintype "bidirectional"))
      (node (ref "IC2") (pin "22") (pinfunction "Y4_22") (pintype "bidirectional"))
    )
    (net (code "22") (name "CAM_Y5") (class "Default")
      (node (ref "IC1") (pin "18") (pinfunction "IO10_18") (pintype "bidirectional"))
      (node (ref "IC2") (pin "20") (pinfunction "Y5_20") (pintype "bidirectional"))
    )
    (net (code "23") (name "CAM_Y6") (class "Default")
      (node (ref "IC1") (pin "20") (pinfunction "IO12_20") (pintype "bidirectional"))
      (node (ref "IC2") (pin "18") (pinfunction "Y6_18") (pintype "bidirectional"))
    )
    (net (code "24") (name "CAM_Y7") (class "Default")
      (node (ref "IC1") (pin "11") (pinfunction "IO18_11") (pintype "bidirectional"))
      (node (ref "IC2") (pin "16") (pinfunction "Y7_16") (pintype "bidirectional"))
    )
    (net (code "25") (name "CAM_Y8") (class "Default")
      (node (ref "IC1") (pin "10") (pinfunction "IO17_10") (pintype "bidirectional"))
      (node (ref "IC2") (pin "14") (pinfunction "Y8_14") (pintype "bidirectional"))
    )
    (net (code "26") (name "CAM_Y9") (class "Default")
      (node (ref "IC1") (pin "9") (pinfunction "IO16_9") (pintype "bidirectional"))
      (node (ref "IC2") (pin "12") (pinfunction "Y9_12") (pintype "bidirectional"))
    )
    (net (code "27") (name "DOVDD_2V8") (class "Default")
      (node (ref "C2") (pin "2") (pinfunction "2_2") (pintype "passive"))
      (node (ref "C3") (pin "2") (pinfunction "2_2") (pintype "passive"))
      (node (ref "IC2") (pin "11") (pinfunction "DOVDD_11") (pintype "bidirectional"))
      (node (ref "R20") (pin "2") (pinfunction "2_2") (pintype "passive"))
      (node (ref "R23") (pin "2") (pinfunction "2_2") (pintype "passive"))
      (node (ref "R24") (pin "2") (pinfunction "2_2") (pintype "passive"))
      (node (ref "R3") (pin "2") (pinfunction "2_2") (pintype "passive"))
    )
    (net (code "28") (name "DVDD_1V5") (class "Default")
      (node (ref "C4") (pin "2") (pinfunction "2_2") (pintype "passive"))
      (node (ref "C5") (pin "2") (pinfunction "2_2") (pintype "passive"))
      (node (ref "IC2") (pin "10") (pinfunction "DVDD_10") (pintype "bidirectional"))
      (node (ref "R4") (pin "2") (pinfunction "2_2") (pintype "passive"))
    )
    (net (code "29") (name "EN") (class "Default")
      (node (ref "C15") (pin "2") (pinfunction "2_2") (pintype "passive"))
      (node (ref "IC1") (pin "3") (pinfunction "EN_3") (pintype "bidirectional"))
      (node (ref "R15") (pin "1") (pinfunction "1_1") (pintype "passive"))
      (node (ref "SW1") (pin "2") (pinfunction "S1_2") (pintype "passive"))
      (node (ref "SW1") (pin "3") (pinfunction "S1_3") (pintype "passive"))
    )
    (net (code "30") (name "EN_5V") (class "Default")
      (node (ref "IC1") (pin "23") (pinfunction "IO21_23") (pintype "bidirectional"))
      (node (ref "IC7") (pin "3") (pinfunction "EN_3") (pintype "passive"))
      (node (ref "R5") (pin "2") (pinfunction "2_2") (pintype "passive"))
    )
    (net (code "31") (name "GND") (class "Default")
      (node (ref "C1") (pin "1") (pinfunction "1_1") (pintype "passive"))
      (node (ref "C10") (pin "1") (pinfunction "1_1") (pintype "passive"))
      (node (ref "C11") (pin "1") (pinfunction "1_1") (pintype "passive"))
      (node (ref "C12") (pin "1") (pinfunction "1_1") (pintype "passive"))
      (node (ref "C13") (pin "1") (pinfunction "1_1") (pintype "passive"))
      (node (ref "C14") (pin "1") (pinfunction "1_1") (pintype "passive"))
      (node (ref "C15") (pin "1") (pinfunction "1_1") (pintype "passive"))
      (node (ref "C16") (pin "1") (pinfunction "1_1") (pintype "passive"))
      (node (ref "C17") (pin "1") (pinfunction "1_1") (pintype "passive"))
      (node (ref "C18") (pin "1") (pinfunction "1_1") (pintype "passive"))
      (node (ref "C19") (pin "1") (pinfunction "1_1") (pintype "passive"))
      (node (ref "C2") (pin "1") (pinfunction "1_1") (pintype "passive"))
      (node (ref "C20") (pin "1") (pinfunction "1_1") (pintype "passive"))
      (node (ref "C21") (pin "1") (pinfunction "1_1") (pintype "passive"))
      (node (ref "C22") (pin "1") (pinfunction "1_1") (pintype "passive"))
      (node (ref "C23") (pin "1") (pinfunction "1_1") (pintype "passive"))
      (node (ref "C24") (pin "1") (pinfunction "1_1") (pintype "passive"))
      (node (ref "C25") (pin "1") (pinfunction "1_1") (pintype "passive"))
      (node (ref "C27") (pin "1") (pinfunction "1_1") (pintype "passive"))
      (node (ref "C28") (pin "1") (pinfunction "1_1") (pintype "passive"))
      (node (ref "C29") (pin "1") (pinfunction "1_1") (pintype "passive"))
      (node (ref "C3") (pin "1") (pinfunction "1_1") (pintype "passive"))
      (node (ref "C30") (pin "2") (pinfunction "2_2") (pintype "passive"))
      (node (ref "C31") (pin "2") (pinfunction "2_2") (pintype "passive"))
      (node (ref "C32") (pin "2") (pinfunction "2_2") (pintype "passive"))
      (node (ref "C33") (pin "2") (pinfunction "2_2") (pintype "passive"))
      (node (ref "C4") (pin "1") (pinfunction "1_1") (pintype "passive"))
      (node (ref "C5") (pin "1") (pinfunction "1_1") (pintype "passive"))
      (node (ref "C6") (pin "1") (pinfunction "1_1") (pintype "passive"))
      (node (ref "C7") (pin "1") (pinfunction "1_1") (pintype "passive"))
      (node (ref "C8") (pin "1") (pinfunction "1_1") (pintype "passive"))
      (node (ref "C9") (pin "1") (pinfunction "1_1") (pintype "passive"))
      (node (ref "D1") (pin "2") (pinfunction "GND_2") (pintype "power_in"))
      (node (ref "D2") (pin "1") (pinfunction "GND_1") (pintype "power_in"))
      (node (ref "D2") (pin "4") (pinfunction "~{ON}_4") (pintype "input"))
      (node (ref "D2") (pin "5") (pinfunction "GND_5") (pintype "power_in"))
      (node (ref "D3") (pin "3") (pinfunction "A_3") (pintype "passive"))
      (node (ref "IC1") (pin "1") (pinfunction "GND_1") (pintype "power_in"))
      (node (ref "IC1") (pin "40") (pinfunction "GND_40") (pintype "power_in"))
      (node (ref "IC1") (pin "P$1") (pinfunction "GND_P$1") (pintype "power_in"))
      (node (ref "IC1") (pin "P$2") (pinfunction "GND_P$2") (pintype "power_in"))
      (node (ref "IC1") (pin "P$3") (pinfunction "GND_P$3") (pintype "power_in"))
      (node (ref "IC1") (pin "P$4") (pinfunction "GND_P$4") (pintype "power_in"))
      (node (ref "IC1") (pin "P$5") (pinfunction "GND_P$5") (pintype "power_in"))
      (node (ref "IC1") (pin "P$6") (pinfunction "GND_P$6") (pintype "power_in"))
      (node (ref "IC1") (pin "P$7") (pinfunction "GND_P$7") (pintype "power_in"))
      (node (ref "IC1") (pin "P$8") (pinfunction "GND_P$8") (pintype "power_in"))
      (node (ref "IC1") (pin "P$9") (pinfunction "GND_P$9") (pintype "power_in"))
      (node (ref "IC10") (pin "11") (pinfunction "FSYNC_11") (pintype "input"))
      (node (ref "IC10") (pin "18") (pinfunction "GND_18") (pintype "power_in"))
      (node (ref "IC10") (pin "20") (pinfunction "GND_20") (pintype "power_in"))
      (node (ref "IC10") (pin "9") (pinfunction "SDO/AD0_9") (pintype "input"))
      (node (ref "IC11") (pin "1") (pinfunction "GND_1") (pintype "power_in"))
      (node (ref "IC2") (pin "15") (pinfunction "DGND_15") (pintype "bidirectional"))
      (node (ref "IC2") (pin "2") (pinfunction "AGND_2") (pintype "bidirectional"))
      (node (ref "IC3") (pin "2") (pinfunction "GND_2") (pintype "power_in"))
      (node (ref "IC4") (pin "1") (pinfunction "GND_1") (pintype "power_in"))
      (node (ref "IC4") (pin "10") (pinfunction "GND_10") (pintype "power_in"))
      (node (ref "IC4") (pin "8") (pinfunction "GND_8") (pintype "power_in"))
      (node (ref "IC5") (pin "1") (pinfunction "GND_1") (pintype "power_in"))
      (node (ref "IC6") (pin "1") (pinfunction "GND_1") (pintype "power_in"))
      (node (ref "IC7") (pin "2") (pinfunction "GND_2") (pintype "power_in"))
      (node (ref "IC8") (pin "1") (pinfunction "GND_1") (pintype "bidirectional"))
      (node (ref "IC8") (pin "4") (pinfunction "GND_4") (pintype "bidirectional"))
      (node (ref "IC8") (pin "6") (pinfunction "QSTRT_6") (pintype "bidirectional"))
      (node (ref "IC8") (pin "TP") (pinfunction "GND_TP") (pintype "bidirectional"))
      (node (ref "IC9") (pin "A3") (pinfunction "PGND_A3") (pintype "power_in"))
      (node (ref "IC9") (pin "B3") (pinfunction "PGND_B3") (pintype "power_in"))
      (node (ref "IC9") (pin "C3") (pinfunction "PGND_C3") (pintype "power_in"))
      (node (ref "IC9") (pin "D4") (pinfunction "AGND_D4") (pintype "power_in"))
      (node (ref "J1") (pin "GND") (pinfunction "GND_GND") (pintype "power_in"))
      (node (ref "J1") (pin "GND2") (pinfunction "GND_GND2") (pintype "power_in"))
      (node (ref "J1") (pin "S@1") (pinfunction "SHIELD_S@1") (pintype "passive"))
      (node (ref "J1") (pin "S@2") (pinfunction "SHIELD_S@2") (pintype "passive"))
      (node (ref "J1") (pin "S@3") (pinfunction "SHIELD_S@3") (pintype "passive"))
      (node (ref "J1") (pin "S@4") (pinfunction "SHIELD_S@4") (pintype "passive"))
      (node (ref "J1") (pin "S@5") (pinfunction "SHIELD_S@5") (pintype "passive"))
      (node (ref "J1") (pin "S@6") (pinfunction "SHIELD_S@6") (pintype "passive"))
      (node (ref "J1") (pin "S@7") (pinfunction "SHIELD_S@7") (pintype "passive"))
      (node (ref "J1") (pin "S@8") (pinfunction "SHIELD_S@8") (pintype "passive"))
      (node (ref "J1") (pin "S@9") (pinfunction "SHIELD_S@9") (pintype "passive"))
      (node (ref "J3") (pin "2") (pinfunction "2_2") (pintype "passive"))
      (node (ref "J4") (pin "1") (pinfunction "1_1") (pintype "passive"))
      (node (ref "J5") (pin "1") (pinfunction "1_1") (pintype "passive"))
      (node (ref "J6") (pin "1") (pinfunction "1_1") (pintype "passive"))
      (node (ref "R11") (pin "1") (pinfunction "1_1") (pintype "passive"))
      (node (ref "R13") (pin "1") (pinfunction "1_1") (pintype "passive"))
      (node (ref "R14") (pin "1") (pinfunction "1_1") (pintype "passive"))
      (node (ref "R17") (pin "1") (pinfunction "1_1") (pintype "passive"))
      (node (ref "R30") (pin "1") (pinfunction "1_1") (pintype "passive"))
      (node (ref "R31") (pin "1") (pinfunction "1_1") (pintype "passive"))
      (node (ref "R37") (pin "1") (pinfunction "1_1") (pintype "passive"))
      (node (ref "R5") (pin "1") (pinfunction "1_1") (pintype "passive"))
      (node (ref "SD1") (pin "GND") (pinfunction "GND_GND") (pintype "bidirectional"))
      (node (ref "SD1") (pin "GND@1") (pinfunction "GND_GND@1") (pintype "bidirectional"))
      (node (ref "SD1") (pin "GND@2") (pinfunction "GND_GND@2") (pintype "bidirectional"))
      (node (ref "SD1") (pin "SW2") (pinfunction "SW2_SW2") (pintype "bidirectional"))
      (node (ref "SW1") (pin "1") (pinfunction "P1_1") (pintype "passive"))
      (node (ref "SW1") (pin "4") (pinfunction "P1_4") (pintype "passive"))
      (node (ref "SW2") (pin "1") (pinfunction "P1_1") (pintype "passive"))
      (node (ref "SW2") (pin "4") (pinfunction "P1_4") (pintype "passive"))
      (node (ref "SW3") (pin "1") (pinfunction "P1_1") (pintype "passive"))
      (node (ref "SW3") (pin "4") (pinfunction "P1_4") (pintype "passive"))
      (node (ref "SW4") (pin "1") (pinfunction "NO1_1") (pintype "passive"))
    )
    (net (code "32") (name "IO14") (class "Default")
      (node (ref "IC1") (pin "22") (pinfunction "IO14_22") (pintype "bidirectional"))
      (node (ref "R16") (pin "2") (pinfunction "2_2") (pintype "passive"))
    )
    (net (code "33") (name "IO48") (class "Default")
      (node (ref "IC1") (pin "25") (pinfunction "IO48_25") (pintype "bidirectional"))
      (node (ref "R8") (pin "2") (pinfunction "2_2") (pintype "passive"))
    )
    (net (code "34") (name "LED_DIN") (class "Default")
      (node (ref "D1") (pin "3") (pinfunction "DI_3") (pintype "bidirectional"))
      (node (ref "R39") (pin "2") (pinfunction "2_2") (pintype "passive"))
    )
    (net (code "35") (name "LED_LV") (class "Default")
      (node (ref "IC1") (pin "26") (pinfunction "IO45_26") (pintype "bidirectional"))
      (node (ref "R13") (pin "2") (pinfunction "2_2") (pintype "passive"))
      (node (ref "R39") (pin "1") (pinfunction "1_1") (pintype "passive"))
    )
    (net (code "36") (name "LORA_INT") (class "Default")
      (node (ref "D5") (pin "C") (pinfunction "C_C") (pintype "passive"))
      (node (ref "D6") (pin "C") (pinfunction "C_C") (pintype "passive"))
      (node (ref "IC1") (pin "36") (pinfunction "RXD0_36") (pintype "bidirectional"))
      (node (ref "R17") (pin "2") (pinfunction "2_2") (pintype "passive"))
    )
    (net (code "37") (name "LORA_RESET") (class "Default")
      (node (ref "C29") (pin "2") (pinfunction "2_2") (pintype "passive"))
      (node (ref "IC4") (pin "6") (pinfunction "~{RESET}_6") (pintype "input"))
      (node (ref "R7") (pin "1") (pinfunction "1_1") (pintype "passive"))
    )
    (net (code "38") (name "LORA_~{CS}") (class "Default")
      (node (ref "IC1") (pin "37") (pinfunction "TXD0_37") (pintype "bidirectional"))
      (node (ref "IC4") (pin "5") (pinfunction "CS_5") (pintype "input"))
    )
    (net (code "39") (name "MISO") (class "Default")
      (node (ref "IC1") (pin "33") (pinfunction "IO40_33") (pintype "bidirectional"))
      (node (ref "IC4") (pin "2") (pinfunction "MISO_2") (pintype "output"))
      (node (ref "R27") (pin "1") (pinfunction "1_1") (pintype "passive"))
      (node (ref "SD1") (pin "MISO") (pinfunction "MISO/DAT0_MISO") (pintype "bidirectional"))
    )
    (net (code "40") (name "MOSI") (class "Default")
      (node (ref "IC1") (pin "31") (pinfunction "IO38_31") (pintype "bidirectional"))
      (node (ref "IC4") (pin "3") (pinfunction "MOSI_3") (pintype "input"))
      (node (ref "R26") (pin "1") (pinfunction "1_1") (pintype "passive"))
      (node (ref "SD1") (pin "MOSI") (pinfunction "MOSI/CMD_MOSI") (pintype "bidirectional"))
    )
    (net (code "41") (name "Net-(D4-PadC)") (class "Default")
      (node (ref "D4") (pin "C") (pinfunction "C_C") (pintype "passive"))
      (node (ref "R12") (pin "2") (pinfunction "2_2") (pintype "passive"))
    )
    (net (code "42") (name "Net-(IC1-IO19)") (class "Default")
      (node (ref "IC1") (pin "13") (pinfunction "IO19_13") (pintype "bidirectional"))
      (node (ref "R33") (pin "1") (pinfunction "1_1") (pintype "passive"))
    )
    (net (code "43") (name "Net-(IC1-IO20)") (class "Default")
      (node (ref "IC1") (pin "14") (pinfunction "IO20_14") (pintype "bidirectional"))
      (node (ref "R34") (pin "1") (pinfunction "1_1") (pintype "passive"))
    )
    (net (code "44") (name "Net-(IC3-PROG)") (class "Default")
      (node (ref "IC3") (pin "5") (pinfunction "PROG_5") (pintype "input"))
      (node (ref "R11") (pin "2") (pinfunction "2_2") (pintype "passive"))
    )
    (net (code "45") (name "Net-(IC3-STAT)") (class "Default")
      (node (ref "IC3") (pin "1") (pinfunction "STAT_1") (pintype "open_collector"))
      (node (ref "R12") (pin "1") (pinfunction "1_1") (pintype "passive"))
    )
    (net (code "46") (name "Net-(IC4-ANT)") (class "Default")
      (node (ref "IC4") (pin "9") (pinfunction "ANT_9") (pintype "bidirectional"))
      (node (ref "J2") (pin "FEED") (pinfunction "SIGNAL_FEED") (pintype "bidirectional"))
    )
    (net (code "47") (name "Net-(IC4-DIO0)") (class "Default")
      (node (ref "D5") (pin "A") (pinfunction "A_A") (pintype "passive"))
      (node (ref "IC4") (pin "14") (pinfunction "DIO0_14") (pintype "bidirectional"))
    )
    (net (code "48") (name "Net-(IC4-DIO1)") (class "Default")
      (node (ref "D6") (pin "A") (pinfunction "A_A") (pintype "passive"))
      (node (ref "IC4") (pin "15") (pinfunction "DIO1_15") (pintype "bidirectional"))
    )
    (net (code "49") (name "Net-(IC7-C+)") (class "Default")
      (node (ref "C26") (pin "2") (pinfunction "2_2") (pintype "passive"))
      (node (ref "IC7") (pin "6") (pinfunction "C+_6") (pintype "passive"))
    )
    (net (code "50") (name "Net-(IC7-C-)") (class "Default")
      (node (ref "C26") (pin "1") (pinfunction "1_1") (pintype "passive"))
      (node (ref "IC7") (pin "4") (pinfunction "C-_4") (pintype "passive"))
    )
    (net (code "51") (name "Net-(IC9-BOLX-PadA4)") (class "Default")
      (node (ref "IC9") (pin "A4") (pinfunction "BOLX_A4") (pintype "output"))
      (node (ref "IC9") (pin "B4") (pinfunction "BOLX_B4") (pintype "output"))
      (node (ref "IC9") (pin "C4") (pinfunction "BOLX_C4") (pintype "output"))
      (node (ref "L2") (pin "1") (pinfunction "1_1") (pintype "passive"))
    )
    (net (code "52") (name "Net-(IC9-BULX-PadA2)") (class "Default")
      (node (ref "IC9") (pin "A2") (pinfunction "BULX_A2") (pintype "output"))
      (node (ref "IC9") (pin "B2") (pinfunction "BULX_B2") (pintype "output"))
      (node (ref "IC9") (pin "C2") (pinfunction "BULX_C2") (pintype "output"))
      (node (ref "L2") (pin "2") (pinfunction "2_2") (pintype "passive"))
    )
    (net (code "53") (name "Net-(IC9-CE)") (class "Default")
      (node (ref "IC9") (pin "D2") (pinfunction "CE_D2") (pintype "input"))
      (node (ref "R1") (pin "1") (pinfunction "1_1") (pintype "passive"))
    )
    (net (code "54") (name "Net-(IC10-REGOUT)") (class "Default")
      (node (ref "C10") (pin "2") (pinfunction "2_2") (pintype "passive"))
      (node (ref "IC10") (pin "10") (pinfunction "REGOUT_10") (pintype "power_in"))
    )
    (net (code "55") (name "Net-(IC11-VIN)") (class "Default")
      (node (ref "C21") (pin "2") (pinfunction "2_2") (pintype "passive"))
      (node (ref "C22") (pin "2") (pinfunction "2_2") (pintype "passive"))
      (node (ref "C24") (pin "2") (pinfunction "2_2") (pintype "passive"))
      (node (ref "IC11") (pin "3") (pinfunction "VIN_3") (pintype "power_in"))
      (node (ref "IC5") (pin "3") (pinfunction "VIN_3") (pintype "power_in"))
      (node (ref "IC6") (pin "3") (pinfunction "VIN_3") (pintype "power_in"))
      (node (ref "SW4") (pin "5") (pinfunction "C2_5") (pintype "passive"))
    )
    (net (code "56") (name "Net-(J1-CC1)") (class "Default")
      (node (ref "J1") (pin "A5") (pinfunction "CC1_A5") (pintype "bidirectional"))
      (node (ref "R30") (pin "2") (pinfunction "2_2") (pintype "passive"))
    )
    (net (code "57") (name "Net-(J1-CC2)") (class "Default")
      (node (ref "J1") (pin "B5") (pinfunction "CC2_B5") (pintype "bidirectional"))
      (node (ref "R31") (pin "2") (pinfunction "2_2") (pintype "passive"))
    )
    (net (code "58") (name "Net-(J2-GND-Pad1)") (class "Default")
      (node (ref "J2") (pin "1") (pinfunction "GND_1") (pintype "bidirectional"))
      (node (ref "J2") (pin "2") (pinfunction "GND_2") (pintype "bidirectional"))
      (node (ref "R37") (pin "2") (pinfunction "2_2") (pintype "passive"))
    )
    (net (code "59") (name "Net-(J6-Pad3)") (class "Default")
      (node (ref "J6") (pin "3") (pinfunction "3_3") (pintype "passive"))
      (node (ref "R8") (pin "1") (pinfunction "1_1") (pintype "passive"))
    )
    (net (code "60") (name "Net-(J6-Pad4)") (class "Default")
      (node (ref "J6") (pin "4") (pinfunction "4_4") (pintype "passive"))
      (node (ref "R16") (pin "1") (pinfunction "1_1") (pintype "passive"))
    )
    (net (code "61") (name "SCK") (class "Default")
      (node (ref "IC1") (pin "32") (pinfunction "IO39_32") (pintype "bidirectional"))
      (node (ref "IC4") (pin "4") (pinfunction "SCK_4") (pintype "input"))
      (node (ref "R28") (pin "1") (pinfunction "1_1") (pintype "passive"))
      (node (ref "SD1") (pin "SCK") (pinfunction "SCK_SCK") (pintype "bidirectional"))
    )
    (net (code "62") (name "SCL") (class "Default")
      (node (ref "IC1") (pin "39") (pinfunction "IO1_39") (pintype "bidirectional"))
      (node (ref "IC8") (pin "7") (pinfunction "SCL_7") (pintype "bidirectional"))
      (node (ref "J4") (pin "4") (pinfunction "4_4") (pintype "passive"))
      (node (ref "R10") (pin "2") (pinfunction "2_2") (pintype "passive"))
      (node (ref "R44") (pin "1") (pinfunction "1_1") (pintype "passive"))
      (node (ref "T8") (pin "6") (pinfunction "D_6") (pintype "passive"))
    )
    (net (code "63") (name "SDA") (class "Default")
      (node (ref "IC1") (pin "38") (pinfunction "IO2_38") (pintype "bidirectional"))
      (node (ref "IC8") (pin "8") (pinfunction "SDA_8") (pintype "bidirectional"))
      (node (ref "J4") (pin "3") (pinfunction "3_3") (pintype "passive"))
      (node (ref "R45") (pin "1") (pinfunction "1_1") (pintype "passive"))
      (node (ref "R9") (pin "2") (pinfunction "2_2") (pintype "passive"))
      (node (ref "T8") (pin "3") (pinfunction "D_3") (pintype "passive"))
    )
    (net (code "64") (name "SDIO_3V3") (class "Default")
      (node (ref "C6") (pin "2") (pinfunction "2_2") (pintype "passive"))
      (node (ref "C7") (pin "2") (pinfunction "2_2") (pintype "passive"))
      (node (ref "Q2") (pin "3") (pinfunction "D_3") (pintype "passive"))
      (node (ref "R26") (pin "2") (pinfunction "2_2") (pintype "passive"))
      (node (ref "R27") (pin "2") (pinfunction "2_2") (pintype "passive"))
      (node (ref "R28") (pin "2") (pinfunction "2_2") (pintype "passive"))
      (node (ref "R29") (pin "2") (pinfunction "2_2") (pintype "passive"))
      (node (ref "SD1") (pin "VCC") (pinfunction "3V3_VCC") (pintype "bidirectional"))
    )
    (net (code "65") (name "SD_ENABLE") (class "Default")
      (node (ref "IC1") (pin "15") (pinfunction "IO3_15") (pintype "bidirectional"))
      (node (ref "Q2") (pin "1") (pinfunction "G_1") (pintype "passive"))
    )
    (net (code "66") (name "SD_SW") (class "Default")
      (node (ref "IC1") (pin "35") (pinfunction "IO42_35") (pintype "bidirectional"))
      (node (ref "R6") (pin "1") (pinfunction "1_1") (pintype "passive"))
      (node (ref "SD1") (pin "SW1") (pinfunction "SW1_SW1") (pintype "bidirectional"))
    )
    (net (code "67") (name "SD_~{CS}") (class "Default")
      (node (ref "IC1") (pin "34") (pinfunction "IO41_34") (pintype "bidirectional"))
      (node (ref "R29") (pin "1") (pinfunction "1_1") (pintype "passive"))
      (node (ref "SD1") (pin "CS") (pinfunction "~{CS}/DAT3_CS") (pintype "bidirectional"))
    )
    (net (code "68") (name "USB-DN") (class "Default")
      (node (ref "D3") (pin "1") (pinfunction "C1_1") (pintype "passive"))
      (node (ref "J1") (pin "A7") (pinfunction "D-_A7") (pintype "bidirectional"))
      (node (ref "J1") (pin "B7") (pinfunction "D-_B7") (pintype "bidirectional"))
      (node (ref "R33") (pin "2") (pinfunction "2_2") (pintype "passive"))
    )
    (net (code "69") (name "USB-DP") (class "Default")
      (node (ref "D3") (pin "2") (pinfunction "C2_2") (pintype "passive"))
      (node (ref "J1") (pin "A6") (pinfunction "D+_A6") (pintype "bidirectional"))
      (node (ref "J1") (pin "B6") (pinfunction "D+_B6") (pintype "bidirectional"))
      (node (ref "R34") (pin "2") (pinfunction "2_2") (pintype "passive"))
    )
    (net (code "70") (name "VBAT") (class "Default")
      (node (ref "C16") (pin "2") (pinfunction "2_2") (pintype "passive"))
      (node (ref "C17") (pin "2") (pinfunction "2_2") (pintype "passive"))
      (node (ref "D2") (pin "6") (pinfunction "VIN2_6") (pintype "power_in"))
      (node (ref "IC3") (pin "3") (pinfunction "VBAT_3") (pintype "bidirectional"))
      (node (ref "IC8") (pin "2") (pinfunction "CELL_2") (pintype "bidirectional"))
      (node (ref "IC8") (pin "3") (pinfunction "VCC_3") (pintype "bidirectional"))
      (node (ref "J3") (pin "1") (pinfunction "1_1") (pintype "passive"))
    )
    (net (code "71") (name "VSWITCHED") (class "Default")
      (node (ref "C25") (pin "2") (pinfunction "2_2") (pintype "passive"))
      (node (ref "C32") (pin "1") (pinfunction "1_1") (pintype "passive"))
      (node (ref "C33") (pin "1") (pinfunction "1_1") (pintype "passive"))
      (node (ref "D2") (pin "2") (pinfunction "VOUT_2") (pintype "power_in"))
      (node (ref "D2") (pin "7") (pinfunction "VOUT_7") (pintype "power_in"))
      (node (ref "IC7") (pin "5") (pinfunction "VIN_5") (pintype "power_in"))
      (node (ref "IC9") (pin "A1") (pinfunction "PVIN_A1") (pintype "power_in"))
      (node (ref "IC9") (pin "B1") (pinfunction "PVIN_B1") (pintype "power_in"))
      (node (ref "IC9") (pin "C1") (pinfunction "PVIN_C1") (pintype "power_in"))
      (node (ref "IC9") (pin "D1") (pinfunction "AVIN_D1") (pintype "power_in"))
      (node (ref "IC9") (pin "D3") (pinfunction "MODE_D3") (pintype "input"))
      (node (ref "SW4") (pin "3") (pinfunction "NC1_3") (pintype "passive"))
      (node (ref "SW4") (pin "6") (pinfunction "NC2_6") (pintype "passive"))
    )
    (net (code "72") (name "VUSB") (class "Default")
      (node (ref "C23") (pin "2") (pinfunction "2_2") (pintype "passive"))
      (node (ref "C28") (pin "2") (pinfunction "2_2") (pintype "passive"))
      (node (ref "D2") (pin "3") (pinfunction "VIN1_3") (pintype "power_in"))
      (node (ref "D4") (pin "A") (pinfunction "A_A") (pintype "passive"))
      (node (ref "IC3") (pin "4") (pinfunction "VIN_4") (pintype "power_in"))
      (node (ref "J1") (pin "VBUS") (pinfunction "VBUS_VBUS") (pintype "power_in"))
      (node (ref "J1") (pin "VBUS2") (pinfunction "VBUS_VBUS2") (pintype "power_in"))
    )
    (net (code "73") (name "V_LED") (class "Default")
      (node (ref "C18") (pin "2") (pinfunction "2_2") (pintype "passive"))
      (node (ref "D1") (pin "4") (pinfunction "VCC_4") (pintype "power_in"))
      (node (ref "R1") (pin "2") (pinfunction "2_2") (pintype "passive"))
      (node (ref "SW4") (pin "2") (pinfunction "C1_2") (pintype "passive"))
    )
    (net (code "74") (name "unconnected-(D1-DO-Pad1)") (class "Default")
      (node (ref "D1") (pin "1") (pinfunction "DO_1") (pintype "bidirectional"))
    )
    (net (code "75") (name "unconnected-(D2-ST-Pad8)") (class "Default")
      (node (ref "D2") (pin "8") (pinfunction "ST_8") (pintype "open_collector"))
    )
    (net (code "76") (name "unconnected-(IC1-IO35-Pad28)") (class "Default")
      (node (ref "IC1") (pin "28") (pinfunction "IO35_28") (pintype "bidirectional"))
    )
    (net (code "77") (name "unconnected-(IC1-IO36-Pad29)") (class "Default")
      (node (ref "IC1") (pin "29") (pinfunction "IO36_29") (pintype "bidirectional"))
    )
    (net (code "78") (name "unconnected-(IC1-IO37-Pad30)") (class "Default")
      (node (ref "IC1") (pin "30") (pinfunction "IO37_30") (pintype "bidirectional"))
    )
    (net (code "79") (name "unconnected-(IC2-NC1-Pad1)") (class "Default")
      (node (ref "IC2") (pin "1") (pinfunction "NC1_1") (pintype "bidirectional"))
    )
    (net (code "80") (name "unconnected-(IC2-Y0-Pad24)") (class "Default")
      (node (ref "IC2") (pin "24") (pinfunction "Y0_24") (pintype "bidirectional"))
    )
    (net (code "81") (name "unconnected-(IC2-Y1-Pad23)") (class "Default")
      (node (ref "IC2") (pin "23") (pinfunction "Y1_23") (pintype "bidirectional"))
    )
    (net (code "82") (name "unconnected-(IC4-DIO2-Pad16)") (class "Default")
      (node (ref "IC4") (pin "16") (pinfunction "DIO2_16") (pintype "bidirectional"))
    )
    (net (code "83") (name "unconnected-(IC4-DIO3-Pad11)") (class "Default")
      (node (ref "IC4") (pin "11") (pinfunction "DIO3_11") (pintype "bidirectional"))
    )
    (net (code "84") (name "unconnected-(IC4-DIO4-Pad12)") (class "Default")
      (node (ref "IC4") (pin "12") (pinfunction "DIO4_12") (pintype "bidirectional"))
    )
    (net (code "85") (name "unconnected-(IC4-DIO5-Pad7)") (class "Default")
      (node (ref "IC4") (pin "7") (pinfunction "DIO5_7") (pintype "bidirectional"))
    )
    (net (code "86") (name "unconnected-(IC8-~{ALERT}-Pad5)") (class "Default")
      (node (ref "IC8") (pin "5") (pinfunction "~{ALERT}_5") (pintype "bidirectional"))
    )
    (net (code "87") (name "unconnected-(IC10-AUX_CL-Pad7)") (class "Default")
      (node (ref "IC10") (pin "7") (pinfunction "AUX_CL_7") (pintype "output"))
    )
    (net (code "88") (name "unconnected-(IC10-AUX_DA-Pad21)") (class "Default")
      (node (ref "IC10") (pin "21") (pinfunction "AUX_DA_21") (pintype "bidirectional"))
    )
    (net (code "89") (name "unconnected-(IC10-INT1-Pad12)") (class "Default")
      (node (ref "IC10") (pin "12") (pinfunction "INT1_12") (pintype "output"))
    )
    (net (code "90") (name "unconnected-(SD1-PadDAT1)") (class "Default")
      (node (ref "SD1") (pin "DAT1") (pinfunction "DAT1_DAT1") (pintype "bidirectional"))
    )
    (net (code "91") (name "unconnected-(SD1-PadDAT2)") (class "Default")
      (node (ref "SD1") (pin "DAT2") (pinfunction "DAT2_DAT2") (pintype "bidirectional"))
    )
    (net (code "92") (name "unconnected-(SW4-NO2-Pad4)") (class "Default")
      (node (ref "SW4") (pin "4") (pinfunction "NO2_4") (pintype "passive"))
    )
  )
)
